# Scheme.net
KiCad netlist of a schematic drawn in Altium Designer
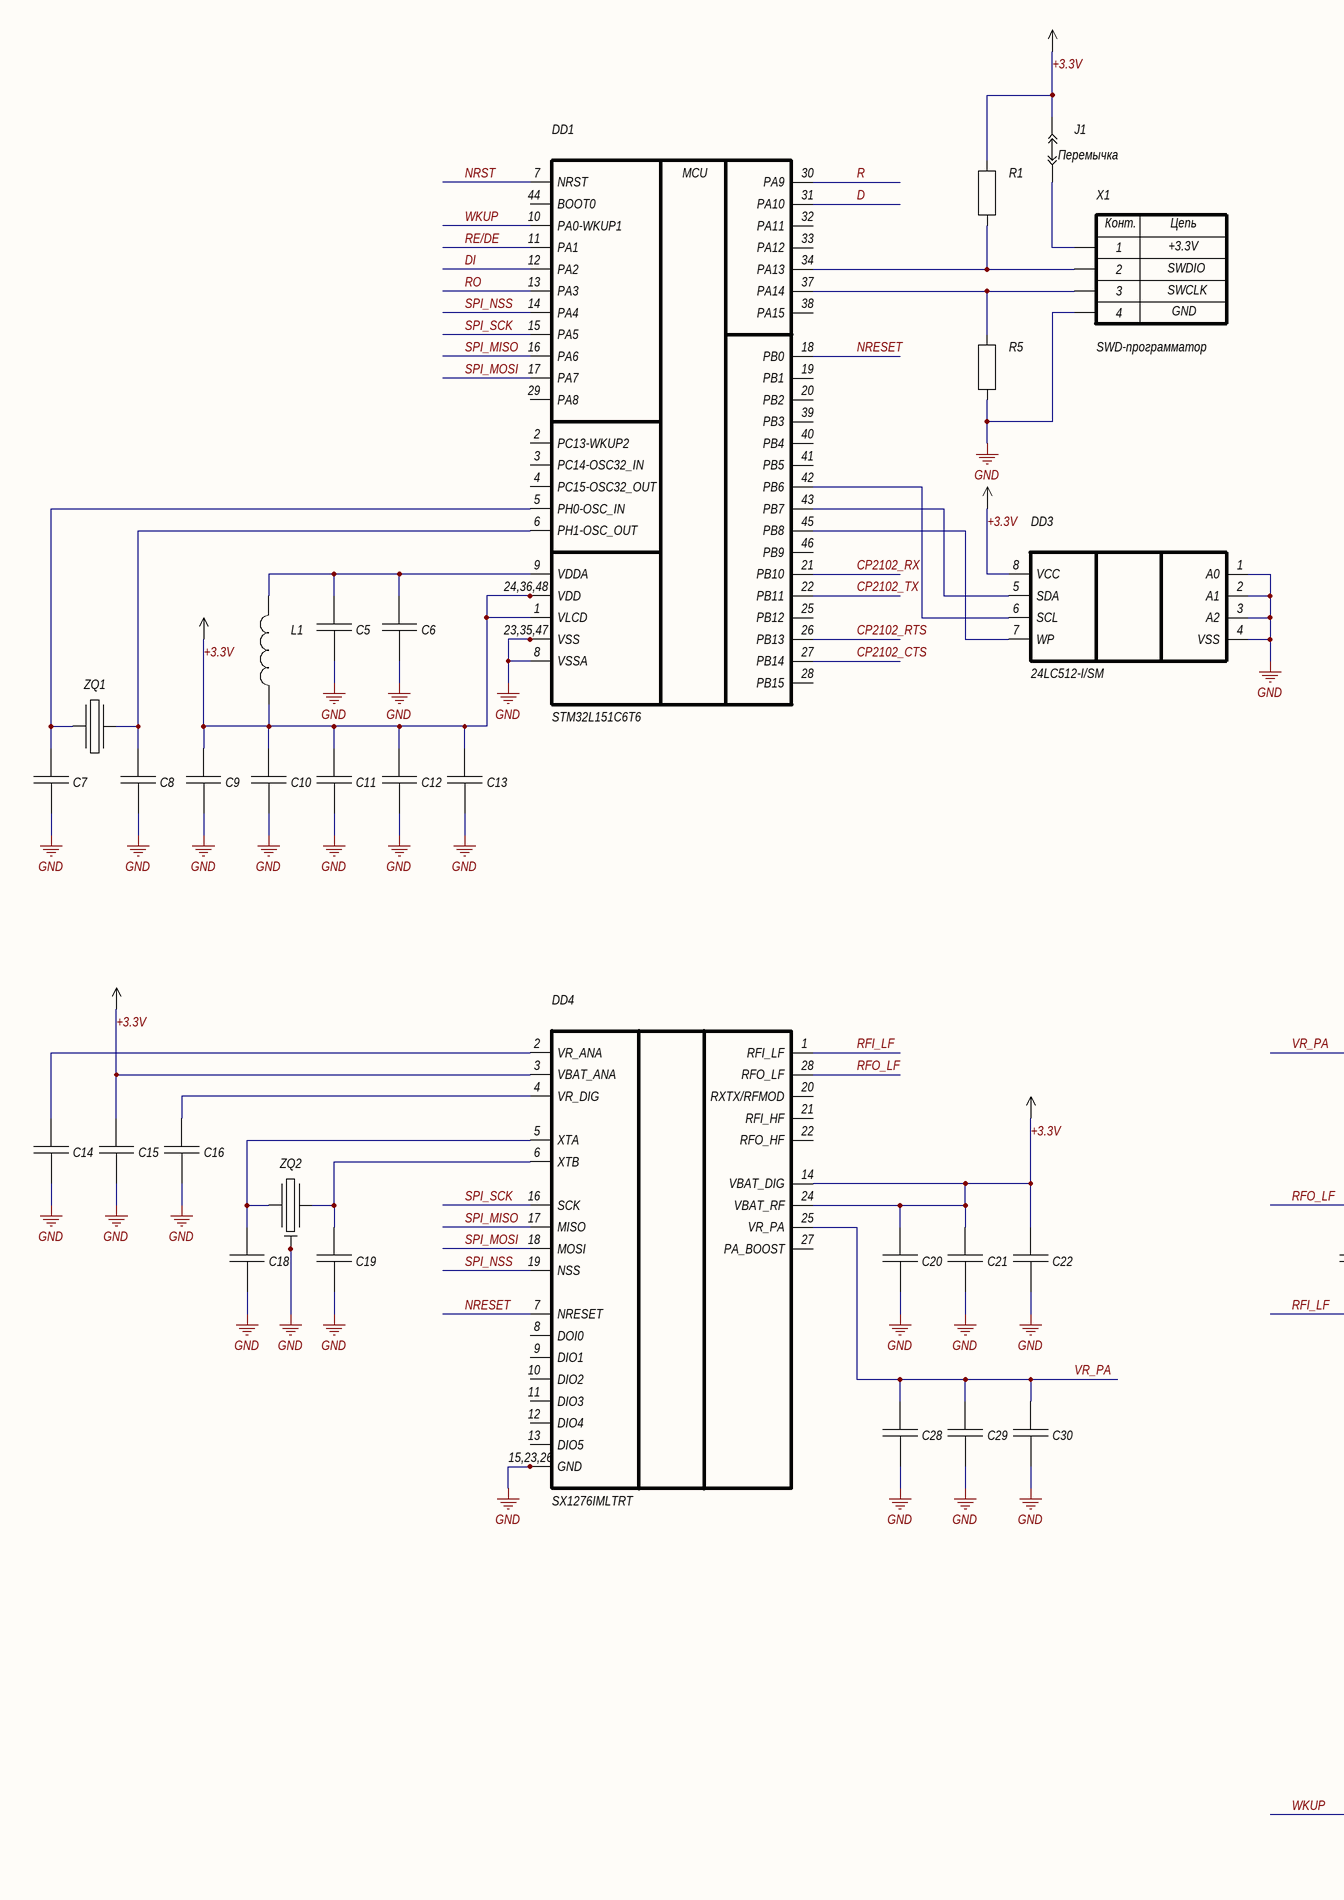
[diagram p0: Scheme.SchDoc, left]
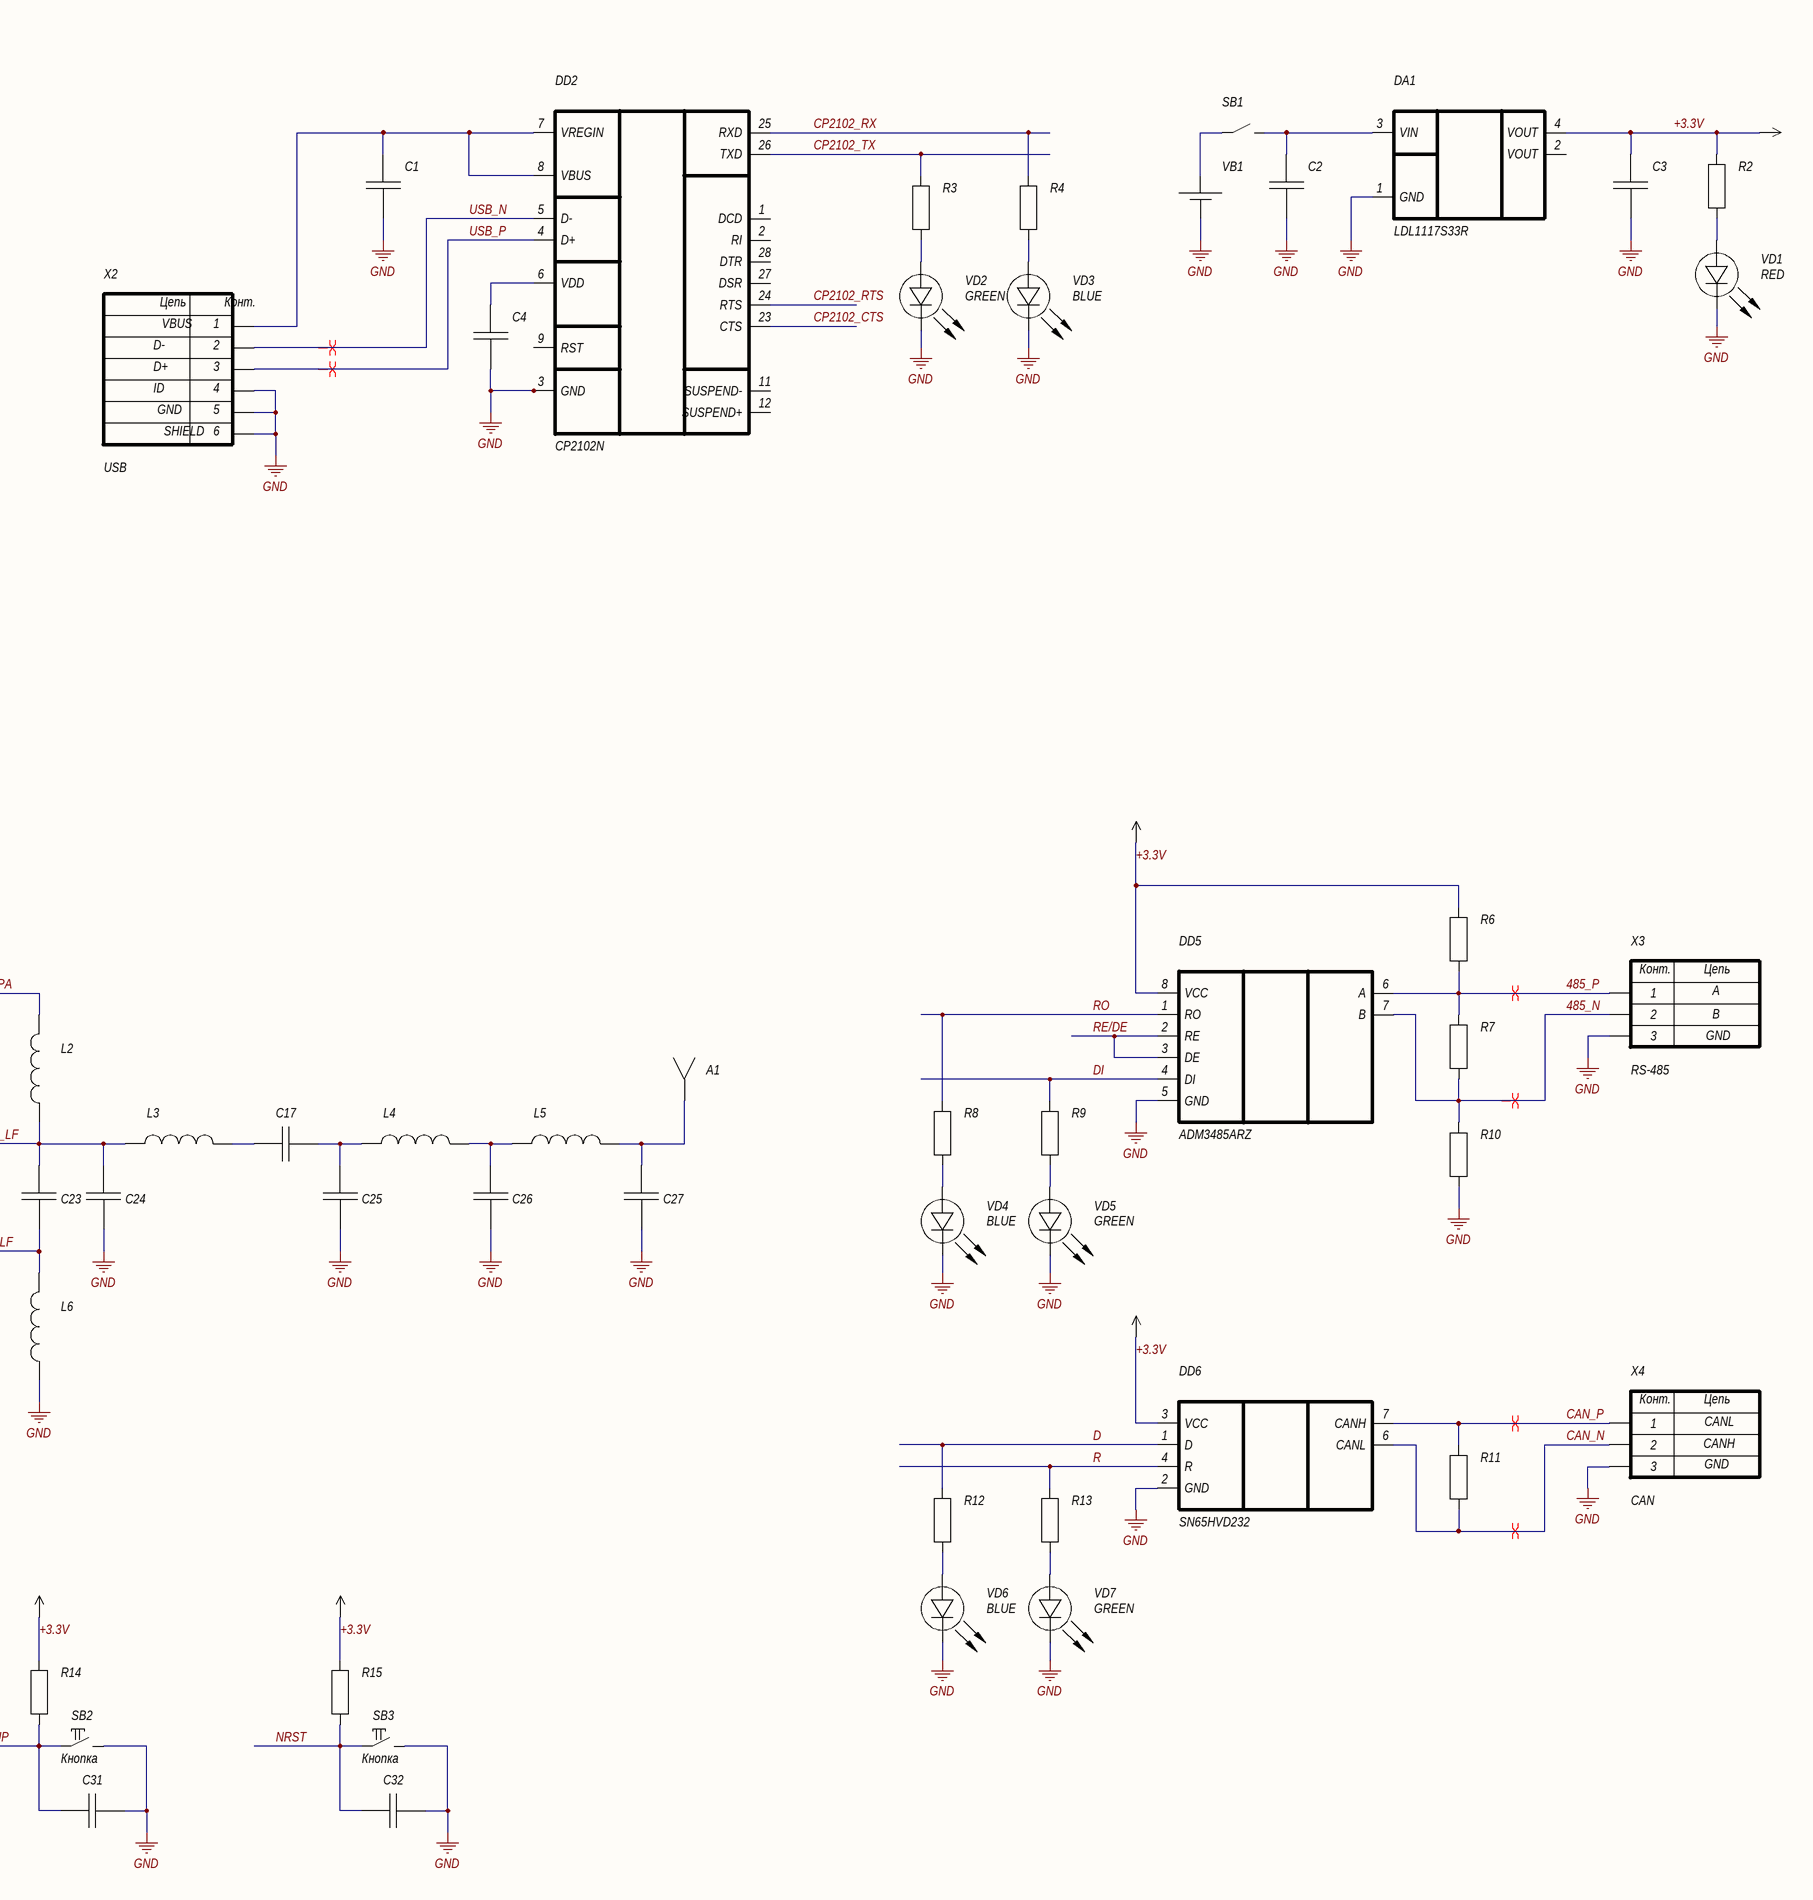
[diagram p1: Scheme.SchDoc, right]

(export (version "E")
  (design (tool "Eeschema 10.0.6"))
  (components
    (comp (ref "*1") (value "PowerLink") (libsource (lib "IC. Power supply") (part "PowerLink")))
    (comp (ref "*2") (value "PowerLink") (libsource (lib "IC. Power supply") (part "PowerLink")))
    (comp (ref "*3") (value "PowerLink") (libsource (lib "IC. Power supply") (part "PowerLink")))
    (comp (ref "*4") (value "PowerLink") (libsource (lib "IC. Power supply") (part "PowerLink")))
    (comp (ref "*5") (value "PowerLink") (libsource (lib "IC. Power supply") (part "PowerLink")))
    (comp (ref "*6") (value "PowerLink") (libsource (lib "IC. Power supply") (part "PowerLink")))
    (comp (ref "*7") (value "PowerLink") (libsource (lib "IC. Power supply") (part "PowerLink")))
    (comp (ref "*8") (value "PowerLink") (libsource (lib "IC. Power supply") (part "PowerLink")))
    (comp (ref "*9") (value "PowerLink") (libsource (lib "IC. Power supply") (part "PowerLink")))
    (comp (ref "*10") (value "PowerLink") (libsource (lib "IC. Power supply") (part "PowerLink")))
    (comp (ref "A1")
      (value "ACAG1204-433-T")
      (footprint "ACAG1204-433-T")
      (description "433 MHz 50 Ohm Chip Antenna")
      (fields (field (name "MANUFACTURER") "Abracon (США)"))
      (libsource (lib "Module") (part "ACAG1204-433-T"))
    )
    (comp (ref "C1")
      (value "Ceramic_0402")
      (footprint "CAP: 0402")
      (fields
        (field (name "MANUFACTURER") "(Китай)")
        (field (name "PARTNUMBER") "CC0402KRX7R7BB104")
        (field (name "VALUEMANUFACTURERPARTNUMBER") "Чип-конденсатор керамический, 100 нФ, X5R, ± 10%, 25 В, 0402, -55...+125°C")
      )
      (libsource (lib "Capacitor") (part "Ceramic_0402"))
    )
    (comp (ref "C2")
      (value "Ceramic_0402")
      (footprint "CAP: 0402")
      (fields
        (field (name "MANUFACTURER") "(Китай)")
        (field (name "PARTNUMBER") "CC0402KRX7R7BB104")
        (field (name "VALUEMANUFACTURERPARTNUMBER") "Чип-конденсатор керамический, 1 мкФ, X5R, ± 10%, 10 В, 0402, -55...+125°C")
      )
      (libsource (lib "Capacitor") (part "Ceramic_0402"))
    )
    (comp (ref "C3")
      (value "Ceramic_0402")
      (footprint "CAP: 0402")
      (fields
        (field (name "MANUFACTURER") "(Китай)")
        (field (name "PARTNUMBER") "CC0402KRX7R7BB104")
        (field (name "VALUEMANUFACTURERPARTNUMBER") "Чип-конденсатор керамический, 4,7 мкФ, X5R, ± 10%, 10 В, 0402, -55...+125°C")
      )
      (libsource (lib "Capacitor") (part "Ceramic_0402"))
    )
    (comp (ref "C4")
      (value "Ceramic_0402")
      (footprint "CAP: 0402")
      (fields
        (field (name "MANUFACTURER") "(Китай)")
        (field (name "PARTNUMBER") "CC0402KRX7R7BB104")
        (field (name "VALUEMANUFACTURERPARTNUMBER") "Чип-конденсатор керамический, 100 нФ, X5R, ± 10%, 25 В, 0402, -55...+125°C")
      )
      (libsource (lib "Capacitor") (part "Ceramic_0402"))
    )
    (comp (ref "C5")
      (value "Ceramic_0402")
      (footprint "CAP: 0402")
      (fields
        (field (name "MANUFACTURER") "(Китай)")
        (field (name "PARTNUMBER") "CC0402KRX7R7BB104")
        (field (name "VALUEMANUFACTURERPARTNUMBER") "Чип-конденсатор керамический, 1 мкФ, X5R, ± 10%, 10 В, 0402, -55...+125°C")
      )
      (libsource (lib "Capacitor") (part "Ceramic_0402"))
    )
    (comp (ref "C6")
      (value "Ceramic_0402")
      (footprint "CAP: 0402")
      (fields
        (field (name "MANUFACTURER") "(Китай)")
        (field (name "PARTNUMBER") "CC0402KRX7R7BB104")
        (field (name "VALUEMANUFACTURERPARTNUMBER") "Чип-конденсатор керамический, 100 нФ, X5R, ± 10%, 25 В, 0402, -55...+125°C")
      )
      (libsource (lib "Capacitor") (part "Ceramic_0402"))
    )
    (comp (ref "C7")
      (value "Ceramic_0402")
      (footprint "CAP: 0402")
      (fields
        (field (name "MANUFACTURER") "(Китай)")
        (field (name "PARTNUMBER") "CC0402KRX7R7BB104")
        (field (name "VALUEMANUFACTURERPARTNUMBER") "Чип-конденсатор керамический, 6 пФ, NPO, ± 0,25 пФ, 50 В, 0402, -55...+125°C")
      )
      (libsource (lib "Capacitor") (part "Ceramic_0402"))
    )
    (comp (ref "C8")
      (value "Ceramic_0402")
      (footprint "CAP: 0402")
      (fields
        (field (name "MANUFACTURER") "(Китай)")
        (field (name "PARTNUMBER") "CC0402KRX7R7BB104")
        (field (name "VALUEMANUFACTURERPARTNUMBER") "Чип-конденсатор керамический, 6 пФ, NPO, ± 0,25 пФ, 50 В, 0402, -55...+125°C")
      )
      (libsource (lib "Capacitor") (part "Ceramic_0402"))
    )
    (comp (ref "C9")
      (value "Ceramic_0402")
      (footprint "CAP: 0402")
      (fields
        (field (name "MANUFACTURER") "(Китай)")
        (field (name "PARTNUMBER") "CC0402KRX7R7BB104")
        (field (name "VALUEMANUFACTURERPARTNUMBER") "Чип-конденсатор керамический, 100 нФ, X5R, ± 10%, 25 В, 0402, -55...+125°C")
      )
      (libsource (lib "Capacitor") (part "Ceramic_0402"))
    )
    (comp (ref "C10")
      (value "Ceramic_0402")
      (footprint "CAP: 0402")
      (fields
        (field (name "MANUFACTURER") "(Китай)")
        (field (name "PARTNUMBER") "CC0402KRX7R7BB104")
        (field (name "VALUEMANUFACTURERPARTNUMBER") "Чип-конденсатор керамический, 100 нФ, X5R, ± 10%, 25 В, 0402, -55...+125°C")
      )
      (libsource (lib "Capacitor") (part "Ceramic_0402"))
    )
    (comp (ref "C11")
      (value "Ceramic_0402")
      (footprint "CAP: 0402")
      (fields
        (field (name "MANUFACTURER") "(Китай)")
        (field (name "PARTNUMBER") "CC0402KRX7R7BB104")
        (field (name "VALUEMANUFACTURERPARTNUMBER") "Чип-конденсатор керамический, 100 нФ, X5R, ± 10%, 25 В, 0402, -55...+125°C")
      )
      (libsource (lib "Capacitor") (part "Ceramic_0402"))
    )
    (comp (ref "C12")
      (value "Ceramic_0402")
      (footprint "CAP: 0402")
      (fields
        (field (name "MANUFACTURER") "(Китай)")
        (field (name "PARTNUMBER") "CC0402KRX7R7BB104")
        (field (name "VALUEMANUFACTURERPARTNUMBER") "Чип-конденсатор керамический, 100 нФ, X5R, ± 10%, 25 В, 0402, -55...+125°C")
      )
      (libsource (lib "Capacitor") (part "Ceramic_0402"))
    )
    (comp (ref "C13")
      (value "Ceramic_0402")
      (footprint "CAP: 0402")
      (fields
        (field (name "MANUFACTURER") "(Китай)")
        (field (name "PARTNUMBER") "CC0402KRX7R7BB104")
        (field (name "VALUEMANUFACTURERPARTNUMBER") "Чип-конденсатор керамический, 1 мкФ, X5R, ± 10%, 10 В, 0402, -55...+125°C")
      )
      (libsource (lib "Capacitor") (part "Ceramic_0402"))
    )
    (comp (ref "C14")
      (value "Ceramic_0402")
      (footprint "CAP: 0402")
      (fields
        (field (name "MANUFACTURER") "(Китай)")
        (field (name "PARTNUMBER") "CC0402KRX7R7BB104")
        (field (name "VALUEMANUFACTURERPARTNUMBER") "Чип-конденсатор керамический, 100 нФ, X5R, ± 10%, 25 В, 0402, -55...+125°C")
      )
      (libsource (lib "Capacitor") (part "Ceramic_0402"))
    )
    (comp (ref "C15")
      (value "Ceramic_0402")
      (footprint "CAP: 0402")
      (fields
        (field (name "MANUFACTURER") "(Китай)")
        (field (name "PARTNUMBER") "CC0402KRX7R7BB104")
        (field (name "VALUEMANUFACTURERPARTNUMBER") "Чип-конденсатор керамический, 100 нФ, X5R, ± 10%, 25 В, 0402, -55...+125°C")
      )
      (libsource (lib "Capacitor") (part "Ceramic_0402"))
    )
    (comp (ref "C16")
      (value "Ceramic_0402")
      (footprint "CAP: 0402")
      (fields
        (field (name "MANUFACTURER") "(Китай)")
        (field (name "PARTNUMBER") "CC0402KRX7R7BB104")
        (field (name "VALUEMANUFACTURERPARTNUMBER") "Чип-конденсатор керамический, 100 нФ, X5R, ± 10%, 25 В, 0402, -55...+125°C")
      )
      (libsource (lib "Capacitor") (part "Ceramic_0402"))
    )
    (comp (ref "C17")
      (value "Ceramic_0402")
      (footprint "CAP: 0402")
      (fields
        (field (name "MANUFACTURER") "(Китай)")
        (field (name "PARTNUMBER") "CC0402KRX7R7BB104")
        (field (name "VALUEMANUFACTURERPARTNUMBER") "Чип-конденсатор керамический, 47 пФ, NPO, ± 5%, 50 В, 0402, -55...+125°C")
      )
      (libsource (lib "Capacitor") (part "Ceramic_0402"))
    )
    (comp (ref "C18")
      (value "Ceramic_0402")
      (footprint "CAP: 0402")
      (fields
        (field (name "MANUFACTURER") "(Китай)")
        (field (name "PARTNUMBER") "CC0402KRX7R7BB104")
        (field (name "VALUEMANUFACTURERPARTNUMBER") "Чип-конденсатор керамический, 6 пФ, NPO, ± 0,25 пФ, 50 В, 0402, -55...+125°C")
      )
      (libsource (lib "Capacitor") (part "Ceramic_0402"))
    )
    (comp (ref "C19")
      (value "Ceramic_0402")
      (footprint "CAP: 0402")
      (fields
        (field (name "MANUFACTURER") "(Китай)")
        (field (name "PARTNUMBER") "CC0402KRX7R7BB104")
        (field (name "VALUEMANUFACTURERPARTNUMBER") "Чип-конденсатор керамический, 6 пФ, NPO, ± 0,25 пФ, 50 В, 0402, -55...+125°C")
      )
      (libsource (lib "Capacitor") (part "Ceramic_0402"))
    )
    (comp (ref "C20")
      (value "Ceramic_0402")
      (footprint "CAP: 0402")
      (fields
        (field (name "MANUFACTURER") "(Китай)")
        (field (name "PARTNUMBER") "CC0402KRX7R7BB104")
        (field (name "VALUEMANUFACTURERPARTNUMBER") "Чип-конденсатор керамический, 100 нФ, X5R, ± 10%, 25 В, 0402, -55...+125°C")
      )
      (libsource (lib "Capacitor") (part "Ceramic_0402"))
    )
    (comp (ref "C21")
      (value "Ceramic_0402")
      (footprint "CAP: 0402")
      (fields
        (field (name "MANUFACTURER") "(Китай)")
        (field (name "PARTNUMBER") "CC0402KRX7R7BB104")
        (field (name "VALUEMANUFACTURERPARTNUMBER") "Чип-конденсатор керамический, 47 пФ, NPO, ± 5%, 50 В, 0402, -55...+125°C")
      )
      (libsource (lib "Capacitor") (part "Ceramic_0402"))
    )
    (comp (ref "C22")
      (value "Ceramic_0402")
      (footprint "CAP: 0402")
      (fields
        (field (name "MANUFACTURER") "(Китай)")
        (field (name "PARTNUMBER") "CC0402KRX7R7BB104")
        (field (name "VALUEMANUFACTURERPARTNUMBER") "Чип-конденсатор керамический, 100 нФ, X5R, ± 10%, 25 В, 0402, -55...+125°C")
      )
      (libsource (lib "Capacitor") (part "Ceramic_0402"))
    )
    (comp (ref "C23")
      (value "Ceramic_0402")
      (footprint "CAP: 0402")
      (fields
        (field (name "MANUFACTURER") "(Китай)")
        (field (name "PARTNUMBER") "CC0402KRX7R7BB104")
        (field (name "VALUEMANUFACTURERPARTNUMBER") "Чип-конденсатор керамический, 2,2 пФ, NPO, ± 0,25 пФ, 50 В, 0402, -55...+125°C")
      )
      (libsource (lib "Capacitor") (part "Ceramic_0402"))
    )
    (comp (ref "C24")
      (value "Ceramic_0402")
      (footprint "CAP: 0402")
      (fields
        (field (name "MANUFACTURER") "(Китай)")
        (field (name "PARTNUMBER") "CC0402KRX7R7BB104")
        (field (name "VALUEMANUFACTURERPARTNUMBER") "Чип-конденсатор керамический, 6,8 пФ, NPO, ± 0,25 пФ, 50 В, 0402, -55...+125°C")
      )
      (libsource (lib "Capacitor") (part "Ceramic_0402"))
    )
    (comp (ref "C25")
      (value "Ceramic_0402")
      (footprint "CAP: 0402")
      (fields
        (field (name "MANUFACTURER") "(Китай)")
        (field (name "PARTNUMBER") "CC0402KRX7R7BB104")
        (field (name "VALUEMANUFACTURERPARTNUMBER") "Чип-конденсатор керамический, 15 пФ, NPO, ± 5%, 50 В, 0402, -55...+125°C")
      )
      (libsource (lib "Capacitor") (part "Ceramic_0402"))
    )
    (comp (ref "C26")
      (value "Ceramic_0402")
      (footprint "CAP: 0402")
      (fields
        (field (name "MANUFACTURER") "(Китай)")
        (field (name "PARTNUMBER") "CC0402KRX7R7BB104")
        (field (name "VALUEMANUFACTURERPARTNUMBER") "Чип-конденсатор керамический, 12 пФ, NPO, ± 5%, 50 В, 0402, -55...+125°C")
      )
      (libsource (lib "Capacitor") (part "Ceramic_0402"))
    )
    (comp (ref "C27")
      (value "Ceramic_0402")
      (footprint "CAP: 0402")
      (fields
        (field (name "MANUFACTURER") "(Китай)")
        (field (name "PARTNUMBER") "CC0402KRX7R7BB104")
        (field (name "VALUEMANUFACTURERPARTNUMBER") "Чип-конденсатор керамический, 6,8 пФ, NPO, ± 0,25 пФ, 50 В, 0402, -55...+125°C")
      )
      (libsource (lib "Capacitor") (part "Ceramic_0402"))
    )
    (comp (ref "C28")
      (value "Ceramic_0402")
      (footprint "CAP: 0402")
      (fields
        (field (name "MANUFACTURER") "(Китай)")
        (field (name "PARTNUMBER") "CC0402KRX7R7BB104")
        (field (name "VALUEMANUFACTURERPARTNUMBER") "Чип-конденсатор керамический, 10 нФ, X7R, ± 10%, 50 В, 0402, -55...+125°C")
      )
      (libsource (lib "Capacitor") (part "Ceramic_0402"))
    )
    (comp (ref "C29")
      (value "Ceramic_0402")
      (footprint "CAP: 0402")
      (fields
        (field (name "MANUFACTURER") "(Китай)")
        (field (name "PARTNUMBER") "CC0402KRX7R7BB104")
        (field (name "VALUEMANUFACTURERPARTNUMBER") "Чип-конденсатор керамический, 47 пФ, NPO, ± 5%, 50 В, 0402, -55...+125°C")
      )
      (libsource (lib "Capacitor") (part "Ceramic_0402"))
    )
    (comp (ref "C30")
      (value "Ceramic_0402")
      (footprint "CAP: 0402")
      (fields
        (field (name "MANUFACTURER") "(Китай)")
        (field (name "PARTNUMBER") "CC0402KRX7R7BB104")
        (field (name "VALUEMANUFACTURERPARTNUMBER") "Чип-конденсатор керамический, 47 пФ, NPO, ± 5%, 50 В, 0402, -55...+125°C")
      )
      (libsource (lib "Capacitor") (part "Ceramic_0402"))
    )
    (comp (ref "C31")
      (value "Ceramic_0402")
      (footprint "CAP: 0402")
      (fields
        (field (name "MANUFACTURER") "(Китай)")
        (field (name "PARTNUMBER") "CC0402KRX7R7BB104")
        (field (name "VALUEMANUFACTURERPARTNUMBER") "Чип-конденсатор керамический, 100 нФ, X5R, ± 10%, 25 В, 0402, -55...+125°C")
      )
      (libsource (lib "Capacitor") (part "Ceramic_0402"))
    )
    (comp (ref "C32")
      (value "Ceramic_0402")
      (footprint "CAP: 0402")
      (fields
        (field (name "MANUFACTURER") "(Китай)")
        (field (name "PARTNUMBER") "CC0402KRX7R7BB104")
        (field (name "VALUEMANUFACTURERPARTNUMBER") "Чип-конденсатор керамический, 100 нФ, X5R, ± 10%, 25 В, 0402, -55...+125°C")
      )
      (libsource (lib "Capacitor") (part "Ceramic_0402"))
    )
    (comp (ref "DA1")
      (value "LDL1117S33R")
      (footprint "SOT223")
      (description "Linear voltage regulator")
      (fields
        (field (name "MANUFACTURER") "STMicroelectronics (США)")
        (field (name "VALUEMANUFACTURERPARTNUMBER") "Linear voltage regulator, input 3.9...18V, 0.6V, output 3.3V, 1.2A, -40...+85°C, SOT223")
        (field (name "PARTNUMBER") "LDL1117S33R")
      )
      (libsource (lib "IC. Power supply") (part "LDL1117S33R"))
    )
    (comp (ref "DD1")
      (value "STM32L151C6T6")
      (footprint "LQFP-48")
      (description "Cortex-M3")
      (fields
        (field (name "MANUFACTURER") "STMicroelectronics (США)")
        (field (name "COPYRIGHT") "Copyright (C) 2016 Accelerated Designs. All rights reserved")
      )
      (libsource (lib "IC. MCU") (part "STM32L151C6T6"))
    )
    (comp (ref "DD2")
      (value "CP2102N")
      (footprint "28-QFN (5x5)")
      (description "USB-to-UART")
      (fields
        (field (name "MANUFACTURER") "Silicon Labs (США)")
        (field (name "VALUEMANUFACTURERPARTNUMBER") "IC usb-to-uart bridge, USB2.0, 3...3.6V, -40...+85°C, 28-VFQFN")
      )
      (libsource (lib "IC. Interface") (part "CP2102N"))
    )
    (comp (ref "DD3")
      (value "24LC512-I/SM")
      (footprint "SOIC8-W_MC")
      (description "No Description Available")
      (fields
        (field (name "MANUFACTURER") "Microchip Technology (США)")
        (field (name "COPYRIGHT") "Copyright (C) 2018 Accelerated Designs. All rights reserved")
      )
      (libsource (lib "IC. Memory") (part "24LC512-I/SM"))
    )
    (comp (ref "DD4")
      (value "SX1276IMLTRT")
      (footprint "28-QFN (6x6)")
      (description "LoRa Transiever")
      (fields
        (field (name "MANUFACTURER") "Semtech Corporation (США)")
        (field (name "COPYRIGHT") "Copyright (C) 2018 Accelerated Designs. All rights reserved")
      )
      (libsource (lib "IC. RF transceiver") (part "SX1276IMLTRT"))
    )
    (comp (ref "DD5")
      (value "ADM3485ARZ")
      (footprint "R_8")
      (description "RS-485-to-UART")
      (fields
        (field (name "MANUFACTURER") "Analog Devices Inc. (США)")
        (field (name "COPYRIGHT") "Copyright (C) 2018 Accelerated Designs. All rights reserved")
      )
      (libsource (lib "IC. Interface") (part "ADM3485ARZ"))
    )
    (comp (ref "DD6")
      (value "SN65HVD232")
      (footprint "D8")
      (description "3.3-V Can Transceiver")
      (fields
        (field (name "MANUFACTURER") "Texas Instruments (США)")
        (field (name "MANUFACTURER_PART_NUMBER") "SN65HVD232D")
        (field (name "COPYRIGHT") "Copyright (C) 2018 Accelerated Designs. All rights reserved")
      )
      (libsource (lib "IC. Interface") (part "SN65HVD232D"))
    )
    (comp (ref "J1")
      (value "~")
      (footprint "CON: JUMPER x1")
      (fields (field (name "COMMENTTEXT") "Перемычка"))
      (libsource (lib "Connector") (part "Jumper_single"))
    )
    (comp (ref "L1")
      (value "Inductor_0603")
      (footprint "IND: 0603")
      (fields
        (field (name "MANUFACTURER") "(Китай)")
        (field (name "PARTNUMBER") "LQM18FN100M00D")
        (field (name "VALUEMANUFACTURERPARTNUMBER") "Чип-индуктивность, 10 мкГн, ± 10%, 0603, 50 мА, -55...+125°C")
      )
      (libsource (lib "Inductor") (part "Inductor_0603"))
    )
    (comp (ref "L2")
      (value "Inductor_0603")
      (footprint "IND: 0603")
      (fields
        (field (name "MANUFACTURER") "(Китай)")
        (field (name "PARTNUMBER") "LQM18FN100M00D")
        (field (name "VALUEMANUFACTURERPARTNUMBER") "Чип-индуктивность, 4,7 нГн, ± 10%, 0603, 50 мА, -55...+125°C")
      )
      (libsource (lib "Inductor") (part "Inductor_0603"))
    )
    (comp (ref "L3")
      (value "Inductor_0603")
      (footprint "IND: 0603")
      (fields
        (field (name "MANUFACTURER") "(Китай)")
        (field (name "PARTNUMBER") "LQM18FN100M00D")
        (field (name "VALUEMANUFACTURERPARTNUMBER") "Чип-индуктивность, 22 нГн, ± 10%, 0603, 50 мА, -55...+125°C")
      )
      (libsource (lib "Inductor") (part "Inductor_0603"))
    )
    (comp (ref "L4")
      (value "Inductor_0603")
      (footprint "IND: 0603")
      (fields
        (field (name "MANUFACTURER") "(Китай)")
        (field (name "PARTNUMBER") "LQM18FN100M00D")
        (field (name "VALUEMANUFACTURERPARTNUMBER") "Чип-индуктивность, 22 нГн, ± 10%, 0603, 50 мА, -55...+125°C")
      )
      (libsource (lib "Inductor") (part "Inductor_0603"))
    )
    (comp (ref "L5")
      (value "Inductor_0603")
      (footprint "IND: 0603")
      (fields
        (field (name "MANUFACTURER") "(Китай)")
        (field (name "PARTNUMBER") "LQM18FN100M00D")
        (field (name "VALUEMANUFACTURERPARTNUMBER") "Чип-индуктивность, 18 нГн, ± 10%, 0603, 50 мА, -55...+125°C")
      )
      (libsource (lib "Inductor") (part "Inductor_0603"))
    )
    (comp (ref "L6")
      (value "Inductor_0603")
      (footprint "IND: 0603")
      (fields
        (field (name "MANUFACTURER") "(Китай)")
        (field (name "PARTNUMBER") "LQM18FN100M00D")
        (field (name "VALUEMANUFACTURERPARTNUMBER") "Чип-индуктивность, 18 нГн, ± 10%, 0603, 50 мА, -55...+125°C")
      )
      (libsource (lib "Inductor") (part "Inductor_0603"))
    )
    (comp (ref "R1")
      (value "Resistor_0402")
      (footprint "RES: 0402")
      (fields
        (field (name "MANUFACTURER") "(Китай)")
        (field (name "PARTNUMBER") "RC0402JR-07100RL")
        (field (name "VALUEMANUFACTURERPARTNUMBER") "Чип-резистор, 10 кОм, ± 5%, 0402, 0,1 Вт, -55...+125°C")
      )
      (libsource (lib "Resistor") (part "Resistor_0402"))
    )
    (comp (ref "R2")
      (value "Resistor_0402")
      (footprint "RES: 0402")
      (fields
        (field (name "MANUFACTURER") "(Китай)")
        (field (name "PARTNUMBER") "RC0402JR-07100RL")
        (field (name "VALUEMANUFACTURERPARTNUMBER") "Чип-резистор, 36 Ом, ± 5%, 0402, 0,1 Вт, -55...+125°C")
      )
      (libsource (lib "Resistor") (part "Resistor_0402"))
    )
    (comp (ref "R3")
      (value "Resistor_0402")
      (footprint "RES: 0402")
      (fields
        (field (name "MANUFACTURER") "(Китай)")
        (field (name "PARTNUMBER") "RC0402JR-07100RL")
        (field (name "VALUEMANUFACTURERPARTNUMBER") "Чип-резистор, 5,1 Ом, ± 5%, 0402, 0,1 Вт, -55...+125°C")
      )
      (libsource (lib "Resistor") (part "Resistor_0402"))
    )
    (comp (ref "R4")
      (value "Resistor_0402")
      (footprint "RES: 0402")
      (fields
        (field (name "MANUFACTURER") "(Китай)")
        (field (name "PARTNUMBER") "RC0402JR-07100RL")
        (field (name "VALUEMANUFACTURERPARTNUMBER") "Чип-резистор, 5,1 Ом, ± 5%, 0402, 0,1 Вт, -55...+125°C")
      )
      (libsource (lib "Resistor") (part "Resistor_0402"))
    )
    (comp (ref "R5")
      (value "Resistor_0402")
      (footprint "RES: 0402")
      (fields
        (field (name "MANUFACTURER") "(Китай)")
        (field (name "PARTNUMBER") "RC0402JR-07100RL")
        (field (name "VALUEMANUFACTURERPARTNUMBER") "Чип-резистор, 10 кОм, ± 5%, 0402, 0,1 Вт, -55...+125°C")
      )
      (libsource (lib "Resistor") (part "Resistor_0402"))
    )
    (comp (ref "R6")
      (value "Resistor_0402")
      (footprint "RES: 0402")
      (fields
        (field (name "MANUFACTURER") "(Китай)")
        (field (name "PARTNUMBER") "RC0402JR-07100RL")
        (field (name "VALUEMANUFACTURERPARTNUMBER") "Чип-резистор, 4,7 кОм, ± 5%, 0402, 0,1 Вт, -55...+125°C")
      )
      (libsource (lib "Resistor") (part "Resistor_0402"))
    )
    (comp (ref "R7")
      (value "Resistor_0402")
      (footprint "RES: 0402")
      (fields
        (field (name "MANUFACTURER") "(Китай)")
        (field (name "PARTNUMBER") "RC0402JR-07100RL")
        (field (name "VALUEMANUFACTURERPARTNUMBER") "Чип-резистор, 120 Ом, ± 5%, 0402, 0,1 Вт, -55...+125°C")
      )
      (libsource (lib "Resistor") (part "Resistor_0402"))
    )
    (comp (ref "R8")
      (value "Resistor_0402")
      (footprint "RES: 0402")
      (fields
        (field (name "MANUFACTURER") "(Китай)")
        (field (name "PARTNUMBER") "RC0402JR-07100RL")
        (field (name "VALUEMANUFACTURERPARTNUMBER") "Чип-резистор, 5,1 Ом, ± 5%, 0402, 0,1 Вт, -55...+125°C")
      )
      (libsource (lib "Resistor") (part "Resistor_0402"))
    )
    (comp (ref "R9")
      (value "Resistor_0402")
      (footprint "RES: 0402")
      (fields
        (field (name "MANUFACTURER") "(Китай)")
        (field (name "PARTNUMBER") "RC0402JR-07100RL")
        (field (name "VALUEMANUFACTURERPARTNUMBER") "Чип-резистор, 5,1 Ом, ± 5%, 0402, 0,1 Вт, -55...+125°C")
      )
      (libsource (lib "Resistor") (part "Resistor_0402"))
    )
    (comp (ref "R10")
      (value "Resistor_0402")
      (footprint "RES: 0402")
      (fields
        (field (name "MANUFACTURER") "(Китай)")
        (field (name "PARTNUMBER") "RC0402JR-07100RL")
        (field (name "VALUEMANUFACTURERPARTNUMBER") "Чип-резистор, 4,7 кОм, ± 5%, 0402, 0,1 Вт, -55...+125°C")
      )
      (libsource (lib "Resistor") (part "Resistor_0402"))
    )
    (comp (ref "R11")
      (value "Resistor_0402")
      (footprint "RES: 0402")
      (fields
        (field (name "MANUFACTURER") "(Китай)")
        (field (name "PARTNUMBER") "RC0402JR-07100RL")
        (field (name "VALUEMANUFACTURERPARTNUMBER") "Чип-резистор, 120 Ом, ± 5%, 0402, 0,1 Вт, -55...+125°C")
      )
      (libsource (lib "Resistor") (part "Resistor_0402"))
    )
    (comp (ref "R12")
      (value "Resistor_0402")
      (footprint "RES: 0402")
      (fields
        (field (name "MANUFACTURER") "(Китай)")
        (field (name "PARTNUMBER") "RC0402JR-07100RL")
        (field (name "VALUEMANUFACTURERPARTNUMBER") "Чип-резистор, 5,1 Ом, ± 5%, 0402, 0,1 Вт, -55...+125°C")
      )
      (libsource (lib "Resistor") (part "Resistor_0402"))
    )
    (comp (ref "R13")
      (value "Resistor_0402")
      (footprint "RES: 0402")
      (fields
        (field (name "MANUFACTURER") "(Китай)")
        (field (name "PARTNUMBER") "RC0402JR-07100RL")
        (field (name "VALUEMANUFACTURERPARTNUMBER") "Чип-резистор, 5,1 Ом, ± 5%, 0402, 0,1 Вт, -55...+125°C")
      )
      (libsource (lib "Resistor") (part "Resistor_0402"))
    )
    (comp (ref "R14")
      (value "Resistor_0402")
      (footprint "RES: 0402")
      (fields
        (field (name "MANUFACTURER") "(Китай)")
        (field (name "PARTNUMBER") "RC0402JR-07100RL")
        (field (name "VALUEMANUFACTURERPARTNUMBER") "Чип-резистор, 1 кОм, ± 5%, 0402, 0,1 Вт, -55...+125°C")
      )
      (libsource (lib "Resistor") (part "Resistor_0402"))
    )
    (comp (ref "R15")
      (value "Resistor_0402")
      (footprint "RES: 0402")
      (fields
        (field (name "MANUFACTURER") "(Китай)")
        (field (name "PARTNUMBER") "RC0402JR-07100RL")
        (field (name "VALUEMANUFACTURERPARTNUMBER") "Чип-резистор, 1 кОм, ± 5%, 0402, 0,1 Вт, -55...+125°C")
      )
      (libsource (lib "Resistor") (part "Resistor_0402"))
    )
    (comp (ref "SB1")
      (value "DS1040-01RT")
      (footprint "DS1040-01RT")
      (description "dip-Switch")
      (fields (field (name "MANUFACTURER") "Ningbo Connfly Electronic (Китай)"))
      (libsource (lib "Electromechanics") (part "DS1040-01RT"))
    )
    (comp (ref "SB2")
      (value "~")
      (footprint "BUT: 6x6 SMD")
      (fields
        (field (name "MANUFACTURER") "Switronic Industrial (Китай)")
        (field (name "VALUEMANUFACTURERPARTNUMBER") "Кнопка тактовая SMD, 6x6x5 мм")
        (field (name "PARTNUMBER") "IT-1102WA8-160G-G")
        (field (name "COMMENTTEXT") "Кнопка")
      )
      (libsource (lib "Electromechanics") (part "Button_tactile"))
    )
    (comp (ref "SB3")
      (value "~")
      (footprint "BUT: 6x6 SMD")
      (fields
        (field (name "MANUFACTURER") "Switronic Industrial (Китай)")
        (field (name "VALUEMANUFACTURERPARTNUMBER") "Кнопка тактовая SMD, 6x6x5 мм")
        (field (name "PARTNUMBER") "IT-1102WA8-160G-G")
        (field (name "COMMENTTEXT") "Кнопка")
      )
      (libsource (lib "Electromechanics") (part "Button_tactile"))
    )
    (comp (ref "VB1")
      (value "AA Battery")
      (footprint "AA Holder")
      (description "AA Battery Holder")
      (fields
        (field (name "PARTNUMBER") "L-KLS5-801-D")
        (field (name "MANUFACTURER") "KLS Electronic Co. (Китай)")
      )
      (libsource (lib "Module") (part "AA Battery"))
    )
    (comp (ref "VD1")
      (value "LED_single")
      (footprint "LED: 0603R")
      (fields
        (field (name "MANUFACTURER") "(Китай)")
        (field (name "VALUEMANUFACTURERPARTNUMBER") "Чип LED-светодиод, Green, *, *, 0603, -55...+150°C")
        (field (name "PARTNUMBER") "BL-HJD36A-AV (HUB36A)")
        (field (name "COLOR") "RED")
      )
      (libsource (lib "Diode") (part "LED_single"))
    )
    (comp (ref "VD2")
      (value "LED_single")
      (footprint "LED: 0603G")
      (fields
        (field (name "MANUFACTURER") "(Китай)")
        (field (name "VALUEMANUFACTURERPARTNUMBER") "Чип LED-светодиод, Green, *, *, 0603, -55...+150°C")
        (field (name "PARTNUMBER") "BL-HG636D")
        (field (name "COLOR") "GREEN")
      )
      (libsource (lib "Diode") (part "LED_single"))
    )
    (comp (ref "VD3")
      (value "LED_single")
      (footprint "LED: 0603B")
      (fields
        (field (name "MANUFACTURER") "(Китай)")
        (field (name "VALUEMANUFACTURERPARTNUMBER") "Чип LED-светодиод, Green, *, *, 0603, -55...+150°C")
        (field (name "PARTNUMBER") "BL-HB536A")
        (field (name "COLOR") "BLUE")
      )
      (libsource (lib "Diode") (part "LED_single"))
    )
    (comp (ref "VD4")
      (value "LED_single")
      (footprint "LED: 0603B")
      (fields
        (field (name "MANUFACTURER") "(Китай)")
        (field (name "VALUEMANUFACTURERPARTNUMBER") "Чип LED-светодиод, Green, *, *, 0603, -55...+150°C")
        (field (name "PARTNUMBER") "BL-HB536A")
        (field (name "COLOR") "BLUE")
      )
      (libsource (lib "Diode") (part "LED_single"))
    )
    (comp (ref "VD5")
      (value "LED_single")
      (footprint "LED: 0603G")
      (fields
        (field (name "MANUFACTURER") "(Китай)")
        (field (name "VALUEMANUFACTURERPARTNUMBER") "Чип LED-светодиод, Green, *, *, 0603, -55...+150°C")
        (field (name "PARTNUMBER") "BL-HG636D")
        (field (name "COLOR") "GREEN")
      )
      (libsource (lib "Diode") (part "LED_single"))
    )
    (comp (ref "VD6")
      (value "LED_single")
      (footprint "LED: 0603B")
      (fields
        (field (name "MANUFACTURER") "(Китай)")
        (field (name "VALUEMANUFACTURERPARTNUMBER") "Чип LED-светодиод, Green, *, *, 0603, -55...+150°C")
        (field (name "PARTNUMBER") "BL-HB536A")
        (field (name "COLOR") "BLUE")
      )
      (libsource (lib "Diode") (part "LED_single"))
    )
    (comp (ref "VD7")
      (value "LED_single")
      (footprint "LED: 0603G")
      (fields
        (field (name "MANUFACTURER") "(Китай)")
        (field (name "VALUEMANUFACTURERPARTNUMBER") "Чип LED-светодиод, Green, *, *, 0603, -55...+150°C")
        (field (name "PARTNUMBER") "BL-HG636D")
        (field (name "COLOR") "GREEN")
      )
      (libsource (lib "Diode") (part "LED_single"))
    )
    (comp (ref "X1")
      (value "~")
      (footprint "CON: PLS-4")
      (fields
        (field (name "MANUFACTURER") "Ningbo Connfly Electronic (Китай)")
        (field (name "VALUEMANUFACTURERPARTNUMBER") "Connector, 4pin, 2,54 мм, 500VAC, 3A")
        (field (name "PARTNUMBER") "DS-1021-1x4")
        (field (name "COMMENTTEXT") "SWD-программатор")
      )
      (libsource (lib "Connector") (part "PLS-4"))
    )
    (comp (ref "X2")
      (value "~")
      (footprint "CON: USB micro-A (ZX62-B-5PA)")
      (fields
        (field (name "MANUFACTURER") "Hirose Electric (Япония)")
        (field (name "VALUEMANUFACTURERPARTNUMBER") "Разъем micro-USB")
        (field (name "PARTNUMBER") "ZX62-B-5PA")
        (field (name "COMMENTTEXT") "USB")
      )
      (libsource (lib "Connector") (part "Connector_USB_micro_B"))
    )
    (comp (ref "X3")
      (value "~")
      (footprint "CON: DG350-3.5-03P")
      (fields
        (field (name "MANUFACTURER") "Degson Electronics (Китай)")
        (field (name "VALUEMANUFACTURERPARTNUMBER") "Клеммник трехконтактный, 3pin, 3.5mm, 300VAC, 10A")
        (field (name "PARTNUMBER") "DG350-3.5-03P-14")
        (field (name "COMMENTTEXT") "RS-485")
      )
      (libsource (lib "Connector") (part "Connector_terminal_3pin"))
    )
    (comp (ref "X4")
      (value "~")
      (footprint "CON: DG350-3.5-03P")
      (fields
        (field (name "MANUFACTURER") "Degson Electronics (Китай)")
        (field (name "VALUEMANUFACTURERPARTNUMBER") "Клеммник трехконтактный, 3pin, 3.5mm, 300VAC, 10A")
        (field (name "PARTNUMBER") "DG350-3.5-03P-14")
        (field (name "COMMENTTEXT") "CAN")
      )
      (libsource (lib "Connector") (part "Connector_terminal_3pin"))
    )
    (comp (ref "ZQ1")
      (value "NX3225GD")
      (footprint "XTAL_NX3225GD-8M")
      (description "8 MHz SMD-Oscillator")
      (fields
        (field (name "MANUFACTURER") "NDK America (США)")
        (field (name "TOLERANCE") "150/50 ppm")
        (field (name "COPYRIGHT") "Copyright (C) 2018 Accelerated Designs. All rights reserved")
      )
      (libsource (lib "Oscilator") (part "NX3225GD"))
    )
    (comp (ref "ZQ2")
      (value "NX3225GA")
      (footprint "NX3225GA-16.000M")
      (description "32 MHz SMD-Oscillator")
      (fields
        (field (name "MANUFACTURER") "NDK America (США)")
        (field (name "TOLERANCE") "15/10 ppm")
        (field (name "COPYRIGHT") "Copyright (C) 2018 Accelerated Designs. All rights reserved")
      )
      (libsource (lib "Oscilator") (part "NX3225SA"))
    )
  )
  (nets
    (net (code "1") (name "/+3.3V") (class "Default")
      (node (ref "*1") (pin "0") (pinfunction "0_0") (pintype "passive"))
      (node (ref "*10") (pin "0") (pinfunction "0_0") (pintype "passive"))
      (node (ref "*2") (pin "0") (pinfunction "0_0") (pintype "passive"))
      (node (ref "*3") (pin "0") (pinfunction "0_0") (pintype "passive"))
      (node (ref "*4") (pin "0") (pinfunction "0_0") (pintype "passive"))
      (node (ref "*5") (pin "0") (pinfunction "0_0") (pintype "passive"))
      (node (ref "*6") (pin "0") (pinfunction "0_0") (pintype "passive"))
      (node (ref "*7") (pin "0") (pinfunction "0_0") (pintype "passive"))
      (node (ref "*8") (pin "0") (pinfunction "0_0") (pintype "passive"))
      (node (ref "*9") (pin "0") (pinfunction "0_0") (pintype "passive"))
      (node (ref "C10") (pin "2") (pinfunction "2_2") (pintype "power_in"))
      (node (ref "C11") (pin "2") (pinfunction "2_2") (pintype "power_in"))
      (node (ref "C12") (pin "2") (pinfunction "2_2") (pintype "power_in"))
      (node (ref "C13") (pin "2") (pinfunction "2_2") (pintype "power_in"))
      (node (ref "C15") (pin "2") (pinfunction "2_2") (pintype "power_in"))
      (node (ref "C20") (pin "2") (pinfunction "2_2") (pintype "power_in"))
      (node (ref "C21") (pin "2") (pinfunction "2_2") (pintype "power_in"))
      (node (ref "C22") (pin "2") (pinfunction "2_2") (pintype "power_in"))
      (node (ref "C3") (pin "2") (pinfunction "2_2") (pintype "power_in"))
      (node (ref "C9") (pin "2") (pinfunction "2_2") (pintype "power_in"))
      (node (ref "DA1") (pin "4") (pinfunction "VOUT_4") (pintype "power_in"))
      (node (ref "DD1") (pin "1") (pinfunction "VLCD_1") (pintype "passive"))
      (node (ref "DD1") (pin "24") (pinfunction "VDD_24") (pintype "passive"))
      (node (ref "DD1") (pin "36") (pinfunction "VDD_2_36") (pintype "passive"))
      (node (ref "DD1") (pin "48") (pinfunction "VDD_3_48") (pintype "passive"))
      (node (ref "DD3") (pin "8") (pinfunction "VCC_8") (pintype "passive"))
      (node (ref "DD4") (pin "14") (pinfunction "VBAT_DIG_14") (pintype "power_in"))
      (node (ref "DD4") (pin "24") (pinfunction "VBAT_RF_24") (pintype "power_in"))
      (node (ref "DD4") (pin "3") (pinfunction "VBAT_ANA_3") (pintype "power_in"))
      (node (ref "DD5") (pin "8") (pinfunction "VCC_8") (pintype "passive"))
      (node (ref "DD6") (pin "3") (pinfunction "VCC_3") (pintype "passive"))
      (node (ref "J1") (pin "2") (pinfunction "IN_2") (pintype "passive"))
      (node (ref "L1") (pin "2") (pinfunction "2_2") (pintype "passive"))
      (node (ref "R1") (pin "2") (pinfunction "2_2") (pintype "passive"))
      (node (ref "R14") (pin "2") (pinfunction "2_2") (pintype "passive"))
      (node (ref "R15") (pin "2") (pinfunction "2_2") (pintype "passive"))
      (node (ref "R2") (pin "2") (pinfunction "2_2") (pintype "passive"))
      (node (ref "R6") (pin "2") (pinfunction "2_2") (pintype "passive"))
    )
    (net (code "2") (name "/485_N") (class "Default")
      (node (ref "DD5") (pin "7") (pinfunction "B_7") (pintype "passive"))
      (node (ref "R10") (pin "2") (pinfunction "2_2") (pintype "passive"))
      (node (ref "R7") (pin "1") (pinfunction "1_1") (pintype "passive"))
      (node (ref "X3") (pin "2") (pinfunction "2_2") (pintype "passive"))
    )
    (net (code "3") (name "/485_P") (class "Default")
      (node (ref "DD5") (pin "6") (pinfunction "A_6") (pintype "passive"))
      (node (ref "R6") (pin "1") (pinfunction "1_1") (pintype "passive"))
      (node (ref "R7") (pin "2") (pinfunction "2_2") (pintype "passive"))
      (node (ref "X3") (pin "1") (pinfunction "1_1") (pintype "passive"))
    )
    (net (code "4") (name "/CAN_N") (class "Default")
      (node (ref "DD6") (pin "6") (pinfunction "CANL_6") (pintype "passive"))
      (node (ref "R11") (pin "1") (pinfunction "1_1") (pintype "passive"))
      (node (ref "X4") (pin "2") (pinfunction "2_2") (pintype "passive"))
    )
    (net (code "5") (name "/CAN_P") (class "Default")
      (node (ref "DD6") (pin "7") (pinfunction "CANH_7") (pintype "passive"))
      (node (ref "R11") (pin "2") (pinfunction "2_2") (pintype "passive"))
      (node (ref "X4") (pin "1") (pinfunction "1_1") (pintype "passive"))
    )
    (net (code "6") (name "/CP2102_CTS") (class "Default")
      (node (ref "DD1") (pin "27") (pinfunction "PB14_27") (pintype "passive"))
      (node (ref "DD2") (pin "23") (pinfunction "CTS_23") (pintype "passive"))
    )
    (net (code "7") (name "/CP2102_RTS") (class "Default")
      (node (ref "DD1") (pin "26") (pinfunction "PB13_26") (pintype "passive"))
      (node (ref "DD2") (pin "24") (pinfunction "RTS_24") (pintype "passive"))
    )
    (net (code "8") (name "/CP2102_RX") (class "Default")
      (node (ref "DD1") (pin "21") (pinfunction "PB10_21") (pintype "passive"))
      (node (ref "DD2") (pin "25") (pinfunction "RXD_25") (pintype "passive"))
      (node (ref "R4") (pin "2") (pinfunction "2_2") (pintype "passive"))
    )
    (net (code "9") (name "/CP2102_TX") (class "Default")
      (node (ref "DD1") (pin "22") (pinfunction "PB11_22") (pintype "passive"))
      (node (ref "DD2") (pin "26") (pinfunction "TXD_26") (pintype "passive"))
      (node (ref "R3") (pin "2") (pinfunction "2_2") (pintype "passive"))
    )
    (net (code "10") (name "/D") (class "Default")
      (node (ref "DD1") (pin "31") (pinfunction "PA10_31") (pintype "passive"))
      (node (ref "DD6") (pin "1") (pinfunction "D_1") (pintype "passive"))
      (node (ref "R12") (pin "2") (pinfunction "2_2") (pintype "passive"))
    )
    (net (code "11") (name "/DI") (class "Default")
      (node (ref "DD1") (pin "12") (pinfunction "PA2_12") (pintype "passive"))
      (node (ref "DD5") (pin "4") (pinfunction "DI_4") (pintype "passive"))
      (node (ref "R9") (pin "2") (pinfunction "2_2") (pintype "passive"))
    )
    (net (code "12") (name "/NRESET") (class "Default")
      (node (ref "DD1") (pin "18") (pinfunction "PB0_18") (pintype "passive"))
      (node (ref "DD4") (pin "7") (pinfunction "NRESET_7") (pintype "power_in"))
    )
    (net (code "13") (name "/NRST") (class "Default")
      (node (ref "C32") (pin "2") (pinfunction "2_2") (pintype "power_in"))
      (node (ref "DD1") (pin "7") (pinfunction "NRST_7") (pintype "passive"))
      (node (ref "R15") (pin "1") (pinfunction "1_1") (pintype "passive"))
      (node (ref "SB3") (pin "1") (pinfunction "1_1") (pintype "passive"))
    )
    (net (code "14") (name "/R") (class "Default")
      (node (ref "DD1") (pin "30") (pinfunction "PA9_30") (pintype "passive"))
      (node (ref "DD6") (pin "4") (pinfunction "R_4") (pintype "passive"))
      (node (ref "R13") (pin "2") (pinfunction "2_2") (pintype "passive"))
    )
    (net (code "15") (name "/RE{slash}DE") (class "Default")
      (node (ref "DD1") (pin "11") (pinfunction "PA1_11") (pintype "passive"))
      (node (ref "DD5") (pin "2") (pinfunction "RE_2") (pintype "passive"))
      (node (ref "DD5") (pin "3") (pinfunction "DE_3") (pintype "passive"))
    )
    (net (code "16") (name "/RFI_LF") (class "Default")
      (node (ref "C23") (pin "1") (pinfunction "1_1") (pintype "power_in"))
      (node (ref "DD4") (pin "1") (pinfunction "RFI_LF_1") (pintype "power_in"))
      (node (ref "L6") (pin "1") (pinfunction "1_1") (pintype "passive"))
    )
    (net (code "17") (name "/RFO_LF") (class "Default")
      (node (ref "C23") (pin "2") (pinfunction "2_2") (pintype "power_in"))
      (node (ref "C24") (pin "2") (pinfunction "2_2") (pintype "power_in"))
      (node (ref "DD4") (pin "28") (pinfunction "RFO_LF_28") (pintype "power_in"))
      (node (ref "L2") (pin "2") (pinfunction "2_2") (pintype "passive"))
      (node (ref "L3") (pin "2") (pinfunction "2_2") (pintype "passive"))
    )
    (net (code "18") (name "/RO") (class "Default")
      (node (ref "DD1") (pin "13") (pinfunction "PA3_13") (pintype "passive"))
      (node (ref "DD5") (pin "1") (pinfunction "RO_1") (pintype "passive"))
      (node (ref "R8") (pin "2") (pinfunction "2_2") (pintype "passive"))
    )
    (net (code "19") (name "/SPI_MISO") (class "Default")
      (node (ref "DD1") (pin "16") (pinfunction "PA6_16") (pintype "passive"))
      (node (ref "DD4") (pin "17") (pinfunction "MISO_17") (pintype "power_in"))
    )
    (net (code "20") (name "/SPI_MOSI") (class "Default")
      (node (ref "DD1") (pin "17") (pinfunction "PA7_17") (pintype "passive"))
      (node (ref "DD4") (pin "18") (pinfunction "MOSI_18") (pintype "power_in"))
    )
    (net (code "21") (name "/SPI_NSS") (class "Default")
      (node (ref "DD1") (pin "14") (pinfunction "PA4_14") (pintype "passive"))
      (node (ref "DD4") (pin "19") (pinfunction "NSS_19") (pintype "power_in"))
    )
    (net (code "22") (name "/SPI_SCK") (class "Default")
      (node (ref "DD1") (pin "15") (pinfunction "PA5_15") (pintype "passive"))
      (node (ref "DD4") (pin "16") (pinfunction "SCK_16") (pintype "power_in"))
    )
    (net (code "23") (name "/USB_N") (class "Default")
      (node (ref "DD2") (pin "5") (pinfunction "D-_5") (pintype "passive"))
      (node (ref "X2") (pin "2") (pinfunction "2_2") (pintype "passive"))
    )
    (net (code "24") (name "/USB_P") (class "Default")
      (node (ref "DD2") (pin "4") (pinfunction "D+_4") (pintype "passive"))
      (node (ref "X2") (pin "3") (pinfunction "3_3") (pintype "passive"))
    )
    (net (code "25") (name "/VR_PA") (class "Default")
      (node (ref "C28") (pin "2") (pinfunction "2_2") (pintype "power_in"))
      (node (ref "C29") (pin "2") (pinfunction "2_2") (pintype "power_in"))
      (node (ref "C30") (pin "2") (pinfunction "2_2") (pintype "power_in"))
      (node (ref "DD4") (pin "25") (pinfunction "VR_PA_25") (pintype "power_in"))
      (node (ref "L2") (pin "1") (pinfunction "1_1") (pintype "passive"))
    )
    (net (code "26") (name "/WKUP") (class "Default")
      (node (ref "C31") (pin "2") (pinfunction "2_2") (pintype "power_in"))
      (node (ref "DD1") (pin "10") (pinfunction "PA0-WKUP1_10") (pintype "passive"))
      (node (ref "R14") (pin "1") (pinfunction "1_1") (pintype "passive"))
      (node (ref "SB2") (pin "1") (pinfunction "1_1") (pintype "passive"))
    )
    (net (code "27") (name "GND") (class "Default")
      (node (ref "C1") (pin "1") (pinfunction "1_1") (pintype "power_in"))
      (node (ref "C10") (pin "1") (pinfunction "1_1") (pintype "power_in"))
      (node (ref "C11") (pin "1") (pinfunction "1_1") (pintype "power_in"))
      (node (ref "C12") (pin "1") (pinfunction "1_1") (pintype "power_in"))
      (node (ref "C13") (pin "1") (pinfunction "1_1") (pintype "power_in"))
      (node (ref "C14") (pin "1") (pinfunction "1_1") (pintype "power_in"))
      (node (ref "C15") (pin "1") (pinfunction "1_1") (pintype "power_in"))
      (node (ref "C16") (pin "1") (pinfunction "1_1") (pintype "power_in"))
      (node (ref "C18") (pin "1") (pinfunction "1_1") (pintype "power_in"))
      (node (ref "C19") (pin "1") (pinfunction "1_1") (pintype "power_in"))
      (node (ref "C2") (pin "1") (pinfunction "1_1") (pintype "power_in"))
      (node (ref "C20") (pin "1") (pinfunction "1_1") (pintype "power_in"))
      (node (ref "C21") (pin "1") (pinfunction "1_1") (pintype "power_in"))
      (node (ref "C22") (pin "1") (pinfunction "1_1") (pintype "power_in"))
      (node (ref "C24") (pin "1") (pinfunction "1_1") (pintype "power_in"))
      (node (ref "C25") (pin "1") (pinfunction "1_1") (pintype "power_in"))
      (node (ref "C26") (pin "1") (pinfunction "1_1") (pintype "power_in"))
      (node (ref "C27") (pin "1") (pinfunction "1_1") (pintype "power_in"))
      (node (ref "C28") (pin "1") (pinfunction "1_1") (pintype "power_in"))
      (node (ref "C29") (pin "1") (pinfunction "1_1") (pintype "power_in"))
      (node (ref "C3") (pin "1") (pinfunction "1_1") (pintype "power_in"))
      (node (ref "C30") (pin "1") (pinfunction "1_1") (pintype "power_in"))
      (node (ref "C31") (pin "1") (pinfunction "1_1") (pintype "power_in"))
      (node (ref "C32") (pin "1") (pinfunction "1_1") (pintype "power_in"))
      (node (ref "C4") (pin "1") (pinfunction "1_1") (pintype "power_in"))
      (node (ref "C5") (pin "1") (pinfunction "1_1") (pintype "power_in"))
      (node (ref "C6") (pin "1") (pinfunction "1_1") (pintype "power_in"))
      (node (ref "C7") (pin "1") (pinfunction "1_1") (pintype "power_in"))
      (node (ref "C8") (pin "1") (pinfunction "1_1") (pintype "power_in"))
      (node (ref "C9") (pin "1") (pinfunction "1_1") (pintype "power_in"))
      (node (ref "DA1") (pin "1") (pinfunction "GND_1") (pintype "power_in"))
      (node (ref "DD1") (pin "23") (pinfunction "VSS_23") (pintype "passive"))
      (node (ref "DD1") (pin "35") (pinfunction "VSS_2_35") (pintype "passive"))
      (node (ref "DD1") (pin "47") (pinfunction "VSS_3_47") (pintype "passive"))
      (node (ref "DD1") (pin "8") (pinfunction "VSSA_8") (pintype "passive"))
      (node (ref "DD2") (pin "0") (pinfunction "PAD_0") (pintype "passive"))
      (node (ref "DD2") (pin "3") (pinfunction "GND_3") (pintype "passive"))
      (node (ref "DD3") (pin "1") (pinfunction "A0_1") (pintype "passive"))
      (node (ref "DD3") (pin "2") (pinfunction "A1_2") (pintype "passive"))
      (node (ref "DD3") (pin "3") (pinfunction "A2_3") (pintype "passive"))
      (node (ref "DD3") (pin "4") (pinfunction "VSS_4") (pintype "passive"))
      (node (ref "DD4") (pin "0") (pinfunction "GND_0") (pintype "power_in"))
      (node (ref "DD4") (pin "15") (pinfunction "GND_15") (pintype "power_in"))
      (node (ref "DD4") (pin "23") (pinfunction "GND_23") (pintype "power_in"))
      (node (ref "DD4") (pin "26") (pinfunction "GND_26") (pintype "power_in"))
      (node (ref "DD5") (pin "5") (pinfunction "GND_5") (pintype "passive"))
      (node (ref "DD6") (pin "2") (pinfunction "GND_2") (pintype "passive"))
      (node (ref "L6") (pin "2") (pinfunction "2_2") (pintype "passive"))
      (node (ref "R10") (pin "1") (pinfunction "1_1") (pintype "passive"))
      (node (ref "R5") (pin "1") (pinfunction "1_1") (pintype "passive"))
      (node (ref "SB2") (pin "2") (pinfunction "2_2") (pintype "passive"))
      (node (ref "SB3") (pin "2") (pinfunction "2_2") (pintype "passive"))
      (node (ref "VB1") (pin "2") (pinfunction "-_2") (pintype "power_in"))
      (node (ref "VD1") (pin "2") (pinfunction "C_2") (pintype "passive"))
      (node (ref "VD2") (pin "2") (pinfunction "C_2") (pintype "passive"))
      (node (ref "VD3") (pin "2") (pinfunction "C_2") (pintype "passive"))
      (node (ref "VD4") (pin "2") (pinfunction "C_2") (pintype "passive"))
      (node (ref "VD5") (pin "2") (pinfunction "C_2") (pintype "passive"))
      (node (ref "VD6") (pin "2") (pinfunction "C_2") (pintype "passive"))
      (node (ref "VD7") (pin "2") (pinfunction "C_2") (pintype "passive"))
      (node (ref "X1") (pin "4") (pinfunction "4_4") (pintype "power_in"))
      (node (ref "X2") (pin "0") (pinfunction "0_0") (pintype "passive"))
      (node (ref "X2") (pin "4") (pinfunction "4_4") (pintype "passive"))
      (node (ref "X2") (pin "5") (pinfunction "5_5") (pintype "passive"))
      (node (ref "X3") (pin "3") (pinfunction "3_3") (pintype "power_in"))
      (node (ref "X4") (pin "3") (pinfunction "3_3") (pintype "power_in"))
      (node (ref "ZQ2") (pin "2") (pinfunction "21_2") (pintype "passive"))
      (node (ref "ZQ2") (pin "4") (pinfunction "4_4") (pintype "passive"))
    )
    (net (code "28") (name "Net-(A1-Pad1)") (class "Default")
      (node (ref "A1") (pin "1") (pinfunction "1_1") (pintype "passive"))
      (node (ref "C27") (pin "2") (pinfunction "2_2") (pintype "power_in"))
      (node (ref "L5") (pin "1") (pinfunction "1_1") (pintype "passive"))
    )
    (net (code "29") (name "Net-(C17-Pad1)") (class "Default")
      (node (ref "C17") (pin "1") (pinfunction "1_1") (pintype "power_in"))
      (node (ref "C25") (pin "2") (pinfunction "2_2") (pintype "power_in"))
      (node (ref "L4") (pin "2") (pinfunction "2_2") (pintype "passive"))
    )
    (net (code "30") (name "Net-(C17-Pad2)") (class "Default")
      (node (ref "C17") (pin "2") (pinfunction "2_2") (pintype "power_in"))
      (node (ref "L3") (pin "1") (pinfunction "1_1") (pintype "passive"))
    )
    (net (code "31") (name "Net-(C26-Pad2)") (class "Default")
      (node (ref "C26") (pin "2") (pinfunction "2_2") (pintype "power_in"))
      (node (ref "L4") (pin "1") (pinfunction "1_1") (pintype "passive"))
      (node (ref "L5") (pin "2") (pinfunction "2_2") (pintype "passive"))
    )
    (net (code "32") (name "Net-(DA1-VIN)") (class "Default")
      (node (ref "C2") (pin "2") (pinfunction "2_2") (pintype "power_in"))
      (node (ref "DA1") (pin "3") (pinfunction "VIN_3") (pintype "power_in"))
      (node (ref "SB1") (pin "2") (pinfunction "2_2") (pintype "passive"))
    )
    (net (code "33") (name "Net-(DD1-PA13)") (class "Default")
      (node (ref "DD1") (pin "34") (pinfunction "PA13_34") (pintype "passive"))
      (node (ref "R1") (pin "1") (pinfunction "1_1") (pintype "passive"))
      (node (ref "X1") (pin "2") (pinfunction "2_2") (pintype "passive"))
    )
    (net (code "34") (name "Net-(DD1-PA14)") (class "Default")
      (node (ref "DD1") (pin "37") (pinfunction "PA14_37") (pintype "passive"))
      (node (ref "R5") (pin "2") (pinfunction "2_2") (pintype "passive"))
      (node (ref "X1") (pin "3") (pinfunction "3_3") (pintype "power_in"))
    )
    (net (code "35") (name "Net-(DD1-PB6)") (class "Default")
      (node (ref "DD1") (pin "42") (pinfunction "PB6_42") (pintype "passive"))
      (node (ref "DD3") (pin "6") (pinfunction "SCL_6") (pintype "passive"))
    )
    (net (code "36") (name "Net-(DD1-PB7)") (class "Default")
      (node (ref "DD1") (pin "43") (pinfunction "PB7_43") (pintype "passive"))
      (node (ref "DD3") (pin "5") (pinfunction "SDA_5") (pintype "passive"))
    )
    (net (code "37") (name "Net-(DD1-PB8)") (class "Default")
      (node (ref "DD1") (pin "45") (pinfunction "PB8_45") (pintype "passive"))
      (node (ref "DD3") (pin "7") (pinfunction "WP_7") (pintype "passive"))
    )
    (net (code "38") (name "Net-(DD1-PH0-OSC_IN)") (class "Default")
      (node (ref "C7") (pin "2") (pinfunction "2_2") (pintype "power_in"))
      (node (ref "DD1") (pin "5") (pinfunction "PH0-OSC_IN_5") (pintype "passive"))
      (node (ref "ZQ1") (pin "1") (pinfunction "1_1") (pintype "passive"))
    )
    (net (code "39") (name "Net-(DD1-PH1-OSC_OUT)") (class "Default")
      (node (ref "C8") (pin "2") (pinfunction "2_2") (pintype "power_in"))
      (node (ref "DD1") (pin "6") (pinfunction "PH1-OSC_OUT_6") (pintype "passive"))
      (node (ref "ZQ1") (pin "2") (pinfunction "2_2") (pintype "passive"))
    )
    (net (code "40") (name "Net-(DD1-VDDA)") (class "Default")
      (node (ref "C5") (pin "2") (pinfunction "2_2") (pintype "power_in"))
      (node (ref "C6") (pin "2") (pinfunction "2_2") (pintype "power_in"))
      (node (ref "DD1") (pin "9") (pinfunction "VDDA_9") (pintype "passive"))
      (node (ref "L1") (pin "1") (pinfunction "1_1") (pintype "passive"))
    )
    (net (code "41") (name "Net-(DD2-VBUS)") (class "Default")
      (node (ref "C1") (pin "2") (pinfunction "2_2") (pintype "power_in"))
      (node (ref "DD2") (pin "7") (pinfunction "VREGIN_7") (pintype "passive"))
      (node (ref "DD2") (pin "8") (pinfunction "VBUS_8") (pintype "passive"))
      (node (ref "X2") (pin "1") (pintype "passive"))
    )
    (net (code "42") (name "Net-(DD2-VDD)") (class "Default")
      (node (ref "C4") (pin "2") (pinfunction "2_2") (pintype "power_in"))
      (node (ref "DD2") (pin "6") (pinfunction "VDD_6") (pintype "passive"))
    )
    (net (code "43") (name "Net-(DD4-VR_ANA)") (class "Default")
      (node (ref "C14") (pin "2") (pinfunction "2_2") (pintype "power_in"))
      (node (ref "DD4") (pin "2") (pinfunction "VR_ANA_2") (pintype "power_in"))
    )
    (net (code "44") (name "Net-(DD4-VR_DIG)") (class "Default")
      (node (ref "C16") (pin "2") (pinfunction "2_2") (pintype "power_in"))
      (node (ref "DD4") (pin "4") (pinfunction "VR_DIG_4") (pintype "power_in"))
    )
    (net (code "45") (name "Net-(DD4-XTA)") (class "Default")
      (node (ref "C18") (pin "2") (pinfunction "2_2") (pintype "power_in"))
      (node (ref "DD4") (pin "5") (pinfunction "XTA_5") (pintype "power_in"))
      (node (ref "ZQ2") (pin "1") (pinfunction "1_1") (pintype "passive"))
    )
    (net (code "46") (name "Net-(DD4-XTB)") (class "Default")
      (node (ref "C19") (pin "2") (pinfunction "2_2") (pintype "power_in"))
      (node (ref "DD4") (pin "6") (pinfunction "XTB_6") (pintype "power_in"))
      (node (ref "ZQ2") (pin "3") (pinfunction "3_3") (pintype "passive"))
    )
    (net (code "47") (name "Net-(J1-IN-Pad1)") (class "Default")
      (node (ref "J1") (pin "1") (pinfunction "IN_1") (pintype "passive"))
      (node (ref "X1") (pin "1") (pinfunction "1_1") (pintype "passive"))
    )
    (net (code "48") (name "Net-(VB1-+)") (class "Default")
      (node (ref "SB1") (pin "1") (pinfunction "1_1") (pintype "passive"))
      (node (ref "VB1") (pin "1") (pinfunction "+_1") (pintype "power_in"))
    )
    (net (code "49") (name "Net-(VD1-A)") (class "Default")
      (node (ref "R2") (pin "1") (pinfunction "1_1") (pintype "passive"))
      (node (ref "VD1") (pin "1") (pinfunction "A_1") (pintype "passive"))
    )
    (net (code "50") (name "Net-(VD2-A)") (class "Default")
      (node (ref "R3") (pin "1") (pinfunction "1_1") (pintype "passive"))
      (node (ref "VD2") (pin "1") (pinfunction "A_1") (pintype "passive"))
    )
    (net (code "51") (name "Net-(VD3-A)") (class "Default")
      (node (ref "R4") (pin "1") (pinfunction "1_1") (pintype "passive"))
      (node (ref "VD3") (pin "1") (pinfunction "A_1") (pintype "passive"))
    )
    (net (code "52") (name "Net-(VD4-A)") (class "Default")
      (node (ref "R8") (pin "1") (pinfunction "1_1") (pintype "passive"))
      (node (ref "VD4") (pin "1") (pinfunction "A_1") (pintype "passive"))
    )
    (net (code "53") (name "Net-(VD5-A)") (class "Default")
      (node (ref "R9") (pin "1") (pinfunction "1_1") (pintype "passive"))
      (node (ref "VD5") (pin "1") (pinfunction "A_1") (pintype "passive"))
    )
    (net (code "54") (name "Net-(VD6-A)") (class "Default")
      (node (ref "R12") (pin "1") (pinfunction "1_1") (pintype "passive"))
      (node (ref "VD6") (pin "1") (pinfunction "A_1") (pintype "passive"))
    )
    (net (code "55") (name "Net-(VD7-A)") (class "Default")
      (node (ref "R13") (pin "1") (pinfunction "1_1") (pintype "passive"))
      (node (ref "VD7") (pin "1") (pinfunction "A_1") (pintype "passive"))
    )
    (net (code "56") (name "unconnected-(DA1-VOUT-Pad2)") (class "Default")
      (node (ref "DA1") (pin "2") (pinfunction "VOUT_2") (pintype "power_in"))
    )
    (net (code "57") (name "unconnected-(DD1-BOOT0-Pad44)") (class "Default")
      (node (ref "DD1") (pin "44") (pinfunction "BOOT0_44") (pintype "passive"))
    )
    (net (code "58") (name "unconnected-(DD1-PA8-Pad29)") (class "Default")
      (node (ref "DD1") (pin "29") (pinfunction "PA8_29") (pintype "passive"))
    )
    (net (code "59") (name "unconnected-(DD1-PA11-Pad32)") (class "Default")
      (node (ref "DD1") (pin "32") (pinfunction "PA11_32") (pintype "passive"))
    )
    (net (code "60") (name "unconnected-(DD1-PA12-Pad33)") (class "Default")
      (node (ref "DD1") (pin "33") (pinfunction "PA12_33") (pintype "passive"))
    )
    (net (code "61") (name "unconnected-(DD1-PA15-Pad38)") (class "Default")
      (node (ref "DD1") (pin "38") (pinfunction "PA15_38") (pintype "passive"))
    )
    (net (code "62") (name "unconnected-(DD1-PB1-Pad19)") (class "Default")
      (node (ref "DD1") (pin "19") (pinfunction "PB1_19") (pintype "passive"))
    )
    (net (code "63") (name "unconnected-(DD1-PB2-Pad20)") (class "Default")
      (node (ref "DD1") (pin "20") (pinfunction "PB2_20") (pintype "passive"))
    )
    (net (code "64") (name "unconnected-(DD1-PB3-Pad39)") (class "Default")
      (node (ref "DD1") (pin "39") (pinfunction "PB3_39") (pintype "passive"))
    )
    (net (code "65") (name "unconnected-(DD1-PB4-Pad40)") (class "Default")
      (node (ref "DD1") (pin "40") (pinfunction "PB4_40") (pintype "passive"))
    )
    (net (code "66") (name "unconnected-(DD1-PB5-Pad41)") (class "Default")
      (node (ref "DD1") (pin "41") (pinfunction "PB5_41") (pintype "passive"))
    )
    (net (code "67") (name "unconnected-(DD1-PB9-Pad46)") (class "Default")
      (node (ref "DD1") (pin "46") (pinfunction "PB9_46") (pintype "passive"))
    )
    (net (code "68") (name "unconnected-(DD1-PB12-Pad25)") (class "Default")
      (node (ref "DD1") (pin "25") (pinfunction "PB12_25") (pintype "passive"))
    )
    (net (code "69") (name "unconnected-(DD1-PB15-Pad28)") (class "Default")
      (node (ref "DD1") (pin "28") (pinfunction "PB15_28") (pintype "passive"))
    )
    (net (code "70") (name "unconnected-(DD1-PC13-WKUP2-Pad2)") (class "Default")
      (node (ref "DD1") (pin "2") (pinfunction "PC13-WKUP2_2") (pintype "passive"))
    )
    (net (code "71") (name "unconnected-(DD1-PC14-OSC32_IN-Pad3)") (class "Default")
      (node (ref "DD1") (pin "3") (pinfunction "PC14-OSC32_IN_3") (pintype "passive"))
    )
    (net (code "72") (name "unconnected-(DD1-PC15-OSC32_OUT-Pad4)") (class "Default")
      (node (ref "DD1") (pin "4") (pinfunction "PC15-OSC32_OUT_4") (pintype "passive"))
    )
    (net (code "73") (name "unconnected-(DD2-DCD-Pad1)") (class "Default")
      (node (ref "DD2") (pin "1") (pinfunction "DCD_1") (pintype "passive"))
    )
    (net (code "74") (name "unconnected-(DD2-DSR-Pad27)") (class "Default")
      (node (ref "DD2") (pin "27") (pinfunction "DSR_27") (pintype "passive"))
    )
    (net (code "75") (name "unconnected-(DD2-DTR-Pad28)") (class "Default")
      (node (ref "DD2") (pin "28") (pinfunction "DTR_28") (pintype "passive"))
    )
    (net (code "76") (name "unconnected-(DD2-RI-Pad2)") (class "Default")
      (node (ref "DD2") (pin "2") (pinfunction "RI_2") (pintype "passive"))
    )
    (net (code "77") (name "unconnected-(DD2-RST-Pad9)") (class "Default")
      (node (ref "DD2") (pin "9") (pinfunction "RST_9") (pintype "passive"))
    )
    (net (code "78") (name "unconnected-(DD2-SUSPEND+-Pad12)") (class "Default")
      (node (ref "DD2") (pin "12") (pinfunction "SUSPEND+_12") (pintype "passive"))
    )
    (net (code "79") (name "unconnected-(DD2-SUSPEND--Pad11)") (class "Default")
      (node (ref "DD2") (pin "11") (pinfunction "SUSPEND-_11") (pintype "passive"))
    )
    (net (code "80") (name "unconnected-(DD4-DIO1-Pad9)") (class "Default")
      (node (ref "DD4") (pin "9") (pinfunction "DIO1_9") (pintype "power_in"))
    )
    (net (code "81") (name "unconnected-(DD4-DIO2-Pad10)") (class "Default")
      (node (ref "DD4") (pin "10") (pinfunction "DIO2_10") (pintype "power_in"))
    )
    (net (code "82") (name "unconnected-(DD4-DIO3-Pad11)") (class "Default")
      (node (ref "DD4") (pin "11") (pinfunction "DIO3_11") (pintype "power_in"))
    )
    (net (code "83") (name "unconnected-(DD4-DIO4-Pad12)") (class "Default")
      (node (ref "DD4") (pin "12") (pinfunction "DIO4_12") (pintype "power_in"))
    )
    (net (code "84") (name "unconnected-(DD4-DIO5-Pad13)") (class "Default")
      (node (ref "DD4") (pin "13") (pinfunction "DIO5_13") (pintype "power_in"))
    )
    (net (code "85") (name "unconnected-(DD4-DOI0-Pad8)") (class "Default")
      (node (ref "DD4") (pin "8") (pinfunction "DOI0_8") (pintype "power_in"))
    )
    (net (code "86") (name "unconnected-(DD4-PA_BOOST-Pad27)") (class "Default")
      (node (ref "DD4") (pin "27") (pinfunction "PA_BOOST_27") (pintype "power_in"))
    )
    (net (code "87") (name "unconnected-(DD4-RFI_HF-Pad21)") (class "Default")
      (node (ref "DD4") (pin "21") (pinfunction "RFI_HF_21") (pintype "power_in"))
    )
    (net (code "88") (name "unconnected-(DD4-RFO_HF-Pad22)") (class "Default")
      (node (ref "DD4") (pin "22") (pinfunction "RFO_HF_22") (pintype "power_in"))
    )
    (net (code "89") (name "unconnected-(DD4-RXTX{slash}RFMOD-Pad20)") (class "Default")
      (node (ref "DD4") (pin "20") (pinfunction "RXTX/RFMOD_20") (pintype "power_in"))
    )
  )
)
